# hello_bord.net
KiCad netlist of a schematic drawn in EAGLE
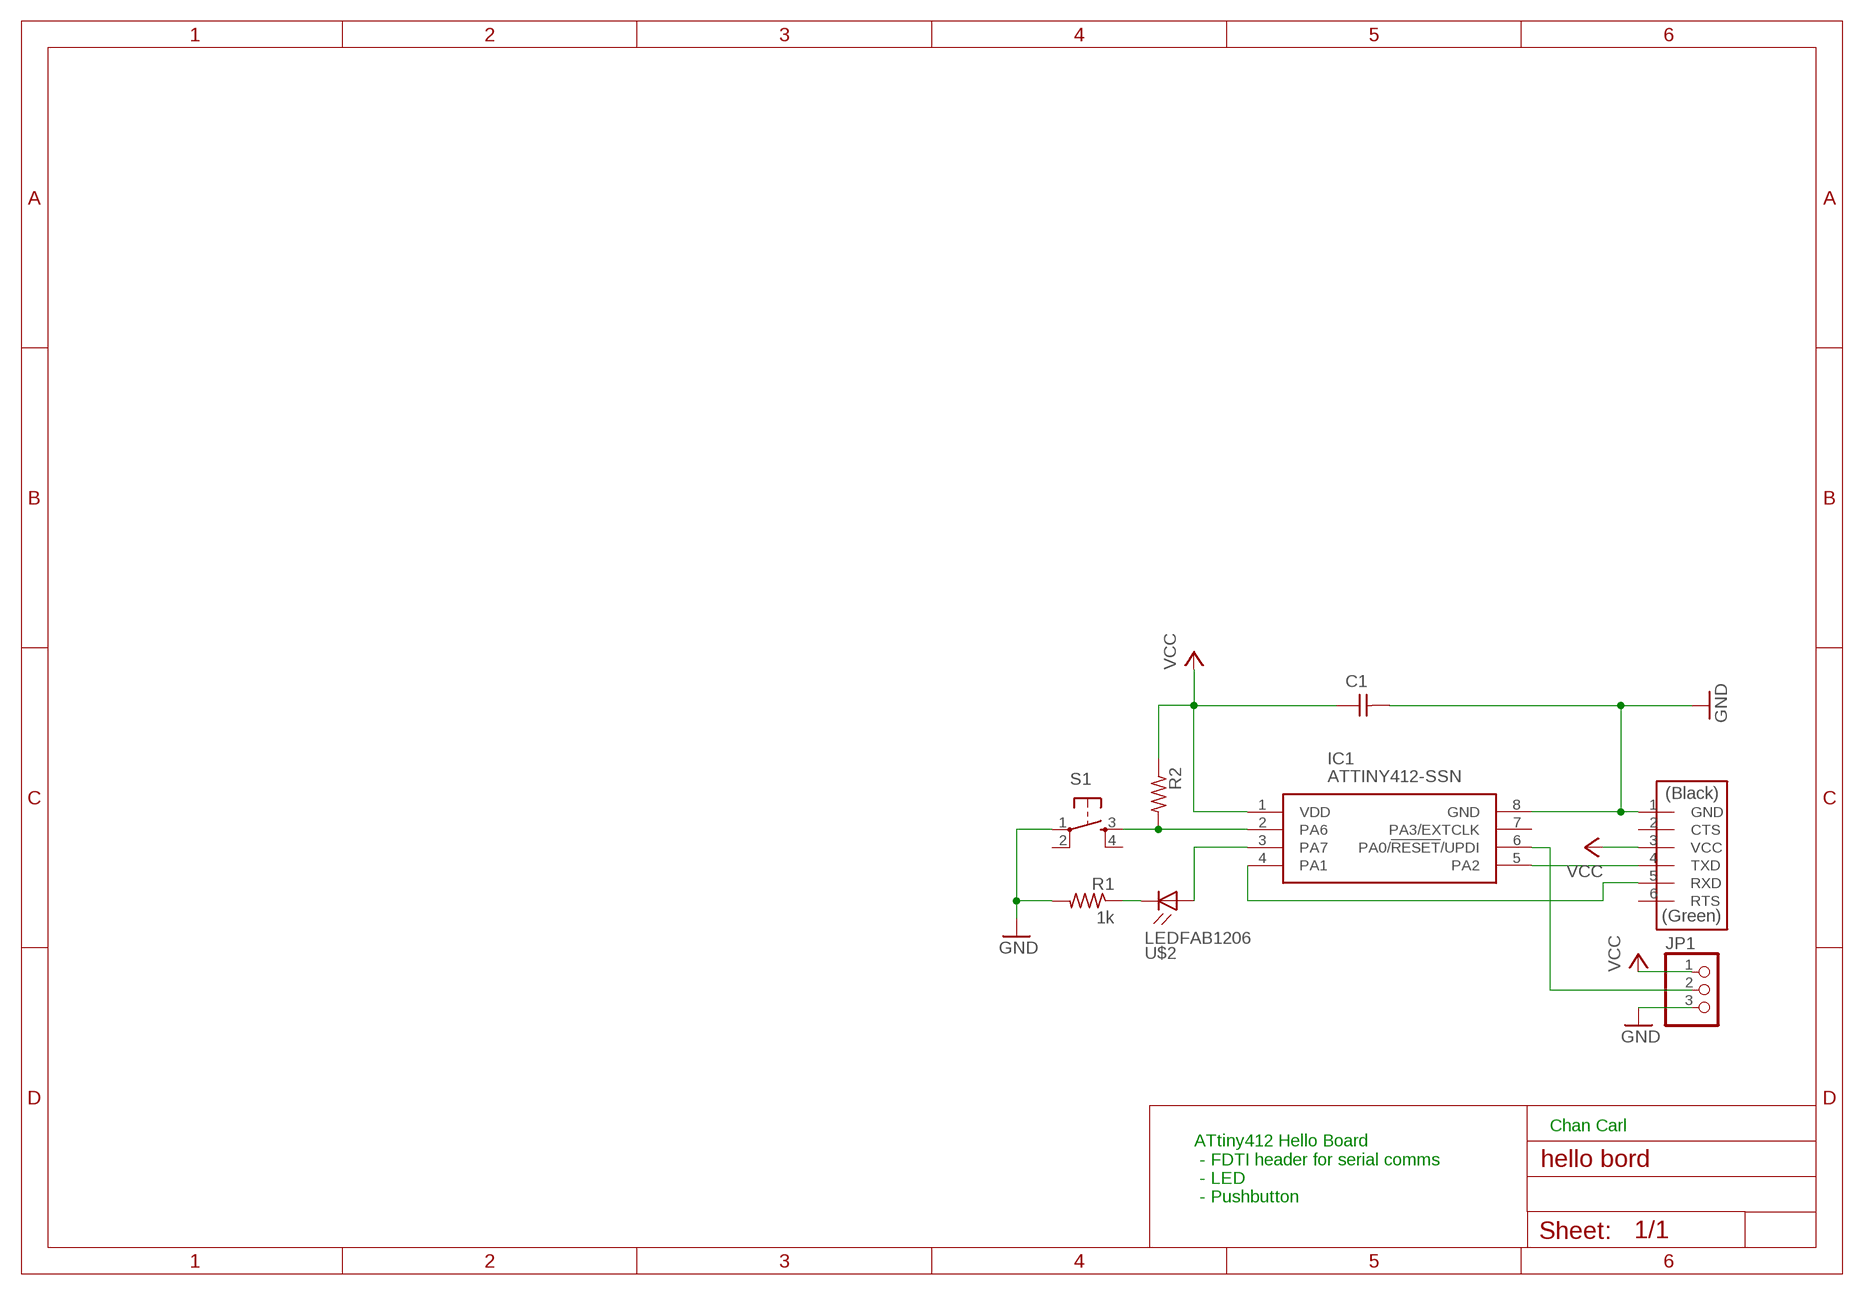
[diagram p0: schematic, sheet 1]

(export (version "E")
  (design (tool "Eeschema 10.0.6"))
  (components
    (comp (ref "C1")
      (value "CAP_UNPOLARIZED")
      (footprint "eagle-import:C1206")
      (libsource (lib "eagle-import") (part "CAP_UNPOLARIZED"))
    )
    (comp (ref "IC1")
      (value "ATTINY412-SSN")
      (footprint "eagle-import:SOIC127P600X175-8N")
      (fields (field (name "MOUSER_PART_NUMBER") "579-ATTINY412-SSN"))
      (libsource (lib "eagle-import") (part "ATTINY412-SSN"))
    )
    (comp (ref "JP1")
      (value "PINHD-1X3")
      (footprint "eagle-import:1X03")
      (libsource (lib "eagle-import") (part "PINHD-1X3"))
    )
    (comp (ref "R1")
      (value "1k")
      (footprint "eagle-import:R1206")
      (libsource (lib "eagle-import") (part "R1206"))
    )
    (comp (ref "R2")
      (value "R1206")
      (footprint "eagle-import:R1206")
      (libsource (lib "eagle-import") (part "R1206"))
    )
    (comp (ref "S1")
      (value "SW_SWITCH_TACTILE_6MM6MM_SWITCH")
      (footprint "eagle-import:6MM_SWITCH")
      (libsource (lib "eagle-import") (part "SW_SWITCH_TACTILE_6MM6MM_SWITCH"))
    )
    (comp (ref "U$1")
      (value "CONN_06_FTDI-SMD-HEADER")
      (footprint "eagle-import:1X06SMD")
      (libsource (lib "eagle-import") (part "CONN_06_FTDI-SMD-HEADER"))
    )
    (comp (ref "U$2")
      (value "LEDFAB1206")
      (footprint "eagle-import:LED1206FAB")
      (libsource (lib "eagle-import") (part "LEDFAB1206"))
    )
  )
  (nets
    (net (code "1") (name "GND") (class "Default")
      (node (ref "C1") (pin "2") (pinfunction "2_2") (pintype "passive"))
      (node (ref "IC1") (pin "8") (pinfunction "GND_8") (pintype "bidirectional"))
      (node (ref "JP1") (pin "3") (pinfunction "3_3") (pintype "passive"))
      (node (ref "R1") (pin "2") (pinfunction "2_2") (pintype "passive"))
      (node (ref "S1") (pin "1") (pinfunction "P_1") (pintype "passive"))
      (node (ref "U$1") (pin "1") (pinfunction "GND_1") (pintype "bidirectional"))
    )
    (net (code "2") (name "Net-(IC1-PA0{slash}~{RESET}{slash}UPDI)") (class "Default")
      (node (ref "IC1") (pin "6") (pinfunction "PA0/~{RESET}/UPDI_6") (pintype "bidirectional"))
      (node (ref "JP1") (pin "2") (pinfunction "2_2") (pintype "passive"))
    )
    (net (code "3") (name "Net-(IC1-PA1)") (class "Default")
      (node (ref "IC1") (pin "4") (pinfunction "PA1_4") (pintype "bidirectional"))
      (node (ref "U$1") (pin "5") (pinfunction "RXD_5") (pintype "bidirectional"))
    )
    (net (code "4") (name "Net-(IC1-PA2)") (class "Default")
      (node (ref "IC1") (pin "5") (pinfunction "PA2_5") (pintype "bidirectional"))
      (node (ref "U$1") (pin "4") (pinfunction "TXD_4") (pintype "bidirectional"))
    )
    (net (code "5") (name "Net-(IC1-PA6)") (class "Default")
      (node (ref "IC1") (pin "2") (pinfunction "PA6_2") (pintype "bidirectional"))
      (node (ref "R2") (pin "2") (pinfunction "2_2") (pintype "passive"))
      (node (ref "S1") (pin "3") (pinfunction "S_3") (pintype "passive"))
    )
    (net (code "6") (name "Net-(IC1-PA7)") (class "Default")
      (node (ref "IC1") (pin "3") (pinfunction "PA7_3") (pintype "bidirectional"))
      (node (ref "U$2") (pin "1") (pinfunction "A_1") (pintype "passive"))
    )
    (net (code "7") (name "Net-(U$2-C)") (class "Default")
      (node (ref "R1") (pin "1") (pinfunction "1_1") (pintype "passive"))
      (node (ref "U$2") (pin "2") (pinfunction "C_2") (pintype "passive"))
    )
    (net (code "8") (name "VCC") (class "Default")
      (node (ref "C1") (pin "1") (pinfunction "1_1") (pintype "passive"))
      (node (ref "IC1") (pin "1") (pinfunction "VDD_1") (pintype "bidirectional"))
      (node (ref "JP1") (pin "1") (pinfunction "1_1") (pintype "passive"))
      (node (ref "R2") (pin "1") (pinfunction "1_1") (pintype "passive"))
      (node (ref "U$1") (pin "3") (pinfunction "VCC_3") (pintype "bidirectional"))
    )
    (net (code "9") (name "unconnected-(IC1-PA3{slash}EXTCLK-Pad7)") (class "Default")
      (node (ref "IC1") (pin "7") (pinfunction "PA3/EXTCLK_7") (pintype "bidirectional"))
    )
    (net (code "10") (name "unconnected-(S1-P1-Pad2)") (class "Default")
      (node (ref "S1") (pin "2") (pinfunction "P1_2") (pintype "passive"))
    )
    (net (code "11") (name "unconnected-(S1-S1-Pad4)") (class "Default")
      (node (ref "S1") (pin "4") (pinfunction "S1_4") (pintype "passive"))
    )
    (net (code "12") (name "unconnected-(U$1-CTS-Pad2)") (class "Default")
      (node (ref "U$1") (pin "2") (pinfunction "CTS_2") (pintype "bidirectional"))
    )
    (net (code "13") (name "unconnected-(U$1-RTS-Pad6)") (class "Default")
      (node (ref "U$1") (pin "6") (pinfunction "RTS_6") (pintype "bidirectional"))
    )
  )
)
